# lab_2_pankov_boost.net
KiCad netlist of a schematic drawn in Altium Designer
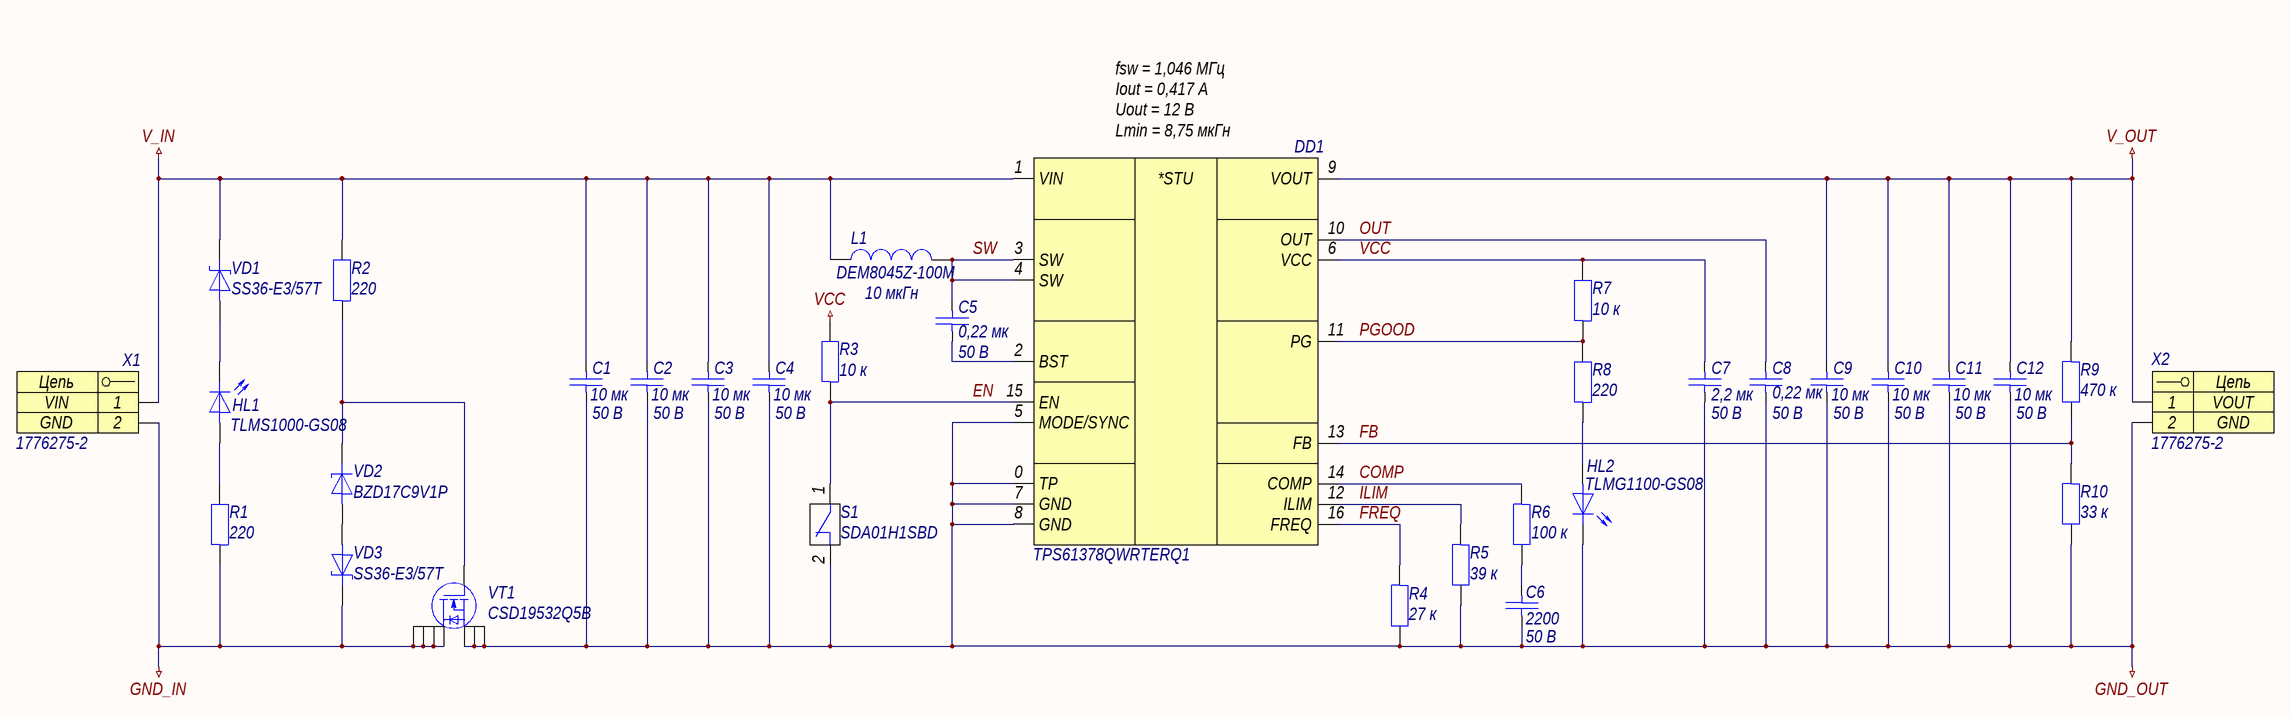
[diagram p0: lab_2_pankov_boost.SchDoc]

(export (version "E")
  (design (tool "Eeschema 10.0.6"))
  (components
    (comp (ref "C1")
      (value "10 мк")
      (footprint "C0805")
      (description "=Описание")
      (fields (field (name "НАПРЯЖЕНИЕ") "50 В"))
      (libsource (lib "Database_Students") (part "C-NONPOLAR"))
    )
    (comp (ref "C2")
      (value "10 мк")
      (footprint "C0805")
      (description "=Описание")
      (fields (field (name "НАПРЯЖЕНИЕ") "50 В"))
      (libsource (lib "Database_Students") (part "C-NONPOLAR"))
    )
    (comp (ref "C3")
      (value "10 мк")
      (footprint "C0805")
      (description "=Описание")
      (fields (field (name "НАПРЯЖЕНИЕ") "50 В"))
      (libsource (lib "Database_Students") (part "C-NONPOLAR"))
    )
    (comp (ref "C4")
      (value "10 мк")
      (footprint "C0805")
      (description "=Описание")
      (fields (field (name "НАПРЯЖЕНИЕ") "50 В"))
      (libsource (lib "Database_Students") (part "C-NONPOLAR"))
    )
    (comp (ref "C5")
      (value "0,22 мк")
      (footprint "C0603")
      (description "=Описание")
      (fields (field (name "НАПРЯЖЕНИЕ") "50 В"))
      (libsource (lib "Database_Students") (part "C-NONPOLAR"))
    )
    (comp (ref "C6")
      (value "2200")
      (footprint "C0603")
      (description "=Описание")
      (fields (field (name "НАПРЯЖЕНИЕ") "50 В"))
      (libsource (lib "Database_Students") (part "C-NONPOLAR"))
    )
    (comp (ref "C7")
      (value "2,2 мк")
      (footprint "C0603")
      (description "=Описание")
      (fields (field (name "НАПРЯЖЕНИЕ") "50 В"))
      (libsource (lib "Database_Students") (part "C-NONPOLAR"))
    )
    (comp (ref "C8")
      (value "0,22 мк")
      (footprint "C0603")
      (description "=Описание")
      (fields (field (name "НАПРЯЖЕНИЕ") "50 В"))
      (libsource (lib "Database_Students") (part "C-NONPOLAR"))
    )
    (comp (ref "C9")
      (value "10 мк")
      (footprint "C0805")
      (description "=Описание")
      (fields (field (name "НАПРЯЖЕНИЕ") "50 В"))
      (libsource (lib "Database_Students") (part "C-NONPOLAR"))
    )
    (comp (ref "C10")
      (value "10 мк")
      (footprint "C0805")
      (description "=Описание")
      (fields (field (name "НАПРЯЖЕНИЕ") "50 В"))
      (libsource (lib "Database_Students") (part "C-NONPOLAR"))
    )
    (comp (ref "C11")
      (value "10 мк")
      (footprint "C0805")
      (description "=Описание")
      (fields (field (name "НАПРЯЖЕНИЕ") "50 В"))
      (libsource (lib "Database_Students") (part "C-NONPOLAR"))
    )
    (comp (ref "C12")
      (value "10 мк")
      (footprint "C0805")
      (description "=Описание")
      (fields (field (name "НАПРЯЖЕНИЕ") "50 В"))
      (libsource (lib "Database_Students") (part "C-NONPOLAR"))
    )
    (comp (ref "DD1")
      (value "TPS61378QWRTERQ1")
      (footprint "QFN-16-3X3")
      (description "=Описание")
      (libsource (lib "Database_Students") (part "TPS61378QWRTERQ1"))
    )
    (comp (ref "HL1")
      (value "TLMS1000-GS08")
      (footprint "HL0603")
      (description "=Описание")
      (libsource (lib "Database_Students") (part "HL-COMMON"))
    )
    (comp (ref "HL2")
      (value "TLMG1100-GS08")
      (footprint "HL0603")
      (description "=Описание")
      (libsource (lib "Database_Students") (part "HL-COMMON"))
    )
    (comp (ref "L1")
      (value "DEM8045Z-100M")
      (footprint "DEM-2-800X800X450")
      (description "=Описание")
      (fields (field (name "ИНДУКТИВНОСТЬ") "10 мкГн"))
      (libsource (lib "Database_Students") (part "INDUCTOR-COMMON"))
    )
    (comp (ref "R1")
      (value "220")
      (footprint "R0603")
      (description "=Описание")
      (libsource (lib "Database_Students") (part "R-COMMON"))
    )
    (comp (ref "R2")
      (value "220")
      (footprint "R0603")
      (description "=Описание")
      (libsource (lib "Database_Students") (part "R-COMMON"))
    )
    (comp (ref "R3")
      (value "10 к")
      (footprint "R0603")
      (description "=Описание")
      (libsource (lib "Database_Students") (part "R-COMMON"))
    )
    (comp (ref "R4")
      (value "27 к")
      (footprint "R0603")
      (description "=Описание")
      (libsource (lib "Database_Students") (part "R-COMMON"))
    )
    (comp (ref "R5")
      (value "39 к")
      (footprint "R0603")
      (description "=Описание")
      (libsource (lib "Database_Students") (part "R-COMMON"))
    )
    (comp (ref "R6")
      (value "100 к")
      (footprint "R0603")
      (description "=Описание")
      (libsource (lib "Database_Students") (part "R-COMMON"))
    )
    (comp (ref "R7")
      (value "10 к")
      (footprint "R0603")
      (description "=Описание")
      (libsource (lib "Database_Students") (part "R-COMMON"))
    )
    (comp (ref "R8")
      (value "220")
      (footprint "R0603")
      (description "=Описание")
      (libsource (lib "Database_Students") (part "R-COMMON"))
    )
    (comp (ref "R9")
      (value "470 к")
      (footprint "R0603")
      (description "=Описание")
      (libsource (lib "Database_Students") (part "R-COMMON"))
    )
    (comp (ref "R10")
      (value "33 к")
      (footprint "R0603")
      (description "=Описание")
      (libsource (lib "Database_Students") (part "R-COMMON"))
    )
    (comp (ref "S1")
      (value "SDA01H1SBD")
      (footprint "DIP-SWITCH-01-452X930X545")
      (description "=Описание")
      (libsource (lib "Database_Students") (part "SWITCH-01"))
    )
    (comp (ref "VD1")
      (value "SS36-E3/57T")
      (footprint "DO-214AB")
      (description "=Описание")
      (libsource (lib "Database_Students") (part "DIODE-SCHOTTKY"))
    )
    (comp (ref "VD2")
      (value "BZD17C9V1P")
      (footprint "DO-219AB")
      (description "=Описание")
      (libsource (lib "Database_Students") (part "ZENER-DIODE"))
    )
    (comp (ref "VD3")
      (value "SS36-E3/57T")
      (footprint "DO-214AB")
      (description "=Описание")
      (libsource (lib "Database_Students") (part "DIODE-SCHOTTKY"))
    )
    (comp (ref "VT1")
      (value "CSD19532Q5B")
      (footprint "SON-8")
      (description "=Описание")
      (libsource (lib "Database_Students") (part "MOSFET_3S_4D"))
    )
    (comp (ref "X1")
      (value "1776275-2")
      (footprint "1776275-2")
      (description "=Описание")
      (libsource (lib "") (part "HEADER-2-TRM_1"))
    )
    (comp (ref "X2")
      (value "1776275-2")
      (footprint "1776275-2")
      (description "=Описание")
      (libsource (lib "Database_Students") (part "HEADER-2-TRM"))
    )
  )
  (nets
    (net (code "1") (name "/COMP") (class "Default")
      (node (ref "DD1") (pin "14") (pinfunction "COMP_14") (pintype "passive"))
      (node (ref "R6") (pin "1") (pinfunction "1_1") (pintype "passive"))
    )
    (net (code "2") (name "/EN") (class "Default")
      (node (ref "DD1") (pin "15") (pinfunction "EN_15") (pintype "passive"))
      (node (ref "R3") (pin "1") (pinfunction "1_1") (pintype "passive"))
      (node (ref "S1") (pin "1") (pinfunction "1_1") (pintype "passive"))
    )
    (net (code "3") (name "/FB") (class "Default")
      (node (ref "DD1") (pin "13") (pinfunction "FB_13") (pintype "passive"))
      (node (ref "R10") (pin "1") (pinfunction "1_1") (pintype "passive"))
      (node (ref "R9") (pin "2") (pinfunction "2_2") (pintype "passive"))
    )
    (net (code "4") (name "/FREQ") (class "Default")
      (node (ref "DD1") (pin "16") (pinfunction "FREQ_16") (pintype "passive"))
      (node (ref "R4") (pin "1") (pinfunction "1_1") (pintype "passive"))
    )
    (net (code "5") (name "/ILIM") (class "Default")
      (node (ref "DD1") (pin "12") (pinfunction "ILIM_12") (pintype "passive"))
      (node (ref "R5") (pin "1") (pinfunction "1_1") (pintype "passive"))
    )
    (net (code "6") (name "/OUT") (class "Default")
      (node (ref "C8") (pin "1") (pinfunction "1_1") (pintype "passive"))
      (node (ref "DD1") (pin "10") (pinfunction "OUT_10") (pintype "passive"))
    )
    (net (code "7") (name "/PGOOD") (class "Default")
      (node (ref "DD1") (pin "11") (pinfunction "PG_11") (pintype "passive"))
      (node (ref "R7") (pin "1") (pinfunction "1_1") (pintype "passive"))
      (node (ref "R8") (pin "2") (pinfunction "2_2") (pintype "passive"))
    )
    (net (code "8") (name "/SW") (class "Default")
      (node (ref "C5") (pin "1") (pinfunction "1_1") (pintype "passive"))
      (node (ref "DD1") (pin "3") (pinfunction "SW_3") (pintype "passive"))
      (node (ref "DD1") (pin "4") (pinfunction "SW_4") (pintype "passive"))
      (node (ref "L1") (pin "2") (pinfunction "2_2") (pintype "passive"))
    )
    (net (code "9") (name "GND_IN") (class "Default")
      (node (ref "R1") (pin "1") (pinfunction "1_1") (pintype "passive"))
      (node (ref "VD3") (pin "1") (pinfunction "1_1") (pintype "passive"))
      (node (ref "VT1") (pin "D") (pinfunction "D_D") (pintype "passive"))
      (node (ref "X1") (pin "2") (pinfunction "2_2") (pintype "passive"))
    )
    (net (code "10") (name "GND_OUT") (class "Default")
      (node (ref "C1") (pin "2") (pinfunction "2_2") (pintype "passive"))
      (node (ref "C10") (pin "2") (pinfunction "2_2") (pintype "passive"))
      (node (ref "C11") (pin "2") (pinfunction "2_2") (pintype "passive"))
      (node (ref "C12") (pin "2") (pinfunction "2_2") (pintype "passive"))
      (node (ref "C2") (pin "2") (pinfunction "2_2") (pintype "passive"))
      (node (ref "C3") (pin "2") (pinfunction "2_2") (pintype "passive"))
      (node (ref "C4") (pin "2") (pinfunction "2_2") (pintype "passive"))
      (node (ref "C6") (pin "1") (pinfunction "1_1") (pintype "passive"))
      (node (ref "C7") (pin "2") (pinfunction "2_2") (pintype "passive"))
      (node (ref "C8") (pin "2") (pinfunction "2_2") (pintype "passive"))
      (node (ref "C9") (pin "2") (pinfunction "2_2") (pintype "passive"))
      (node (ref "DD1") (pin "0") (pinfunction "TP_0") (pintype "passive"))
      (node (ref "DD1") (pin "5") (pinfunction "MODE/SYNC_5") (pintype "passive"))
      (node (ref "DD1") (pin "7") (pinfunction "GND_7") (pintype "passive"))
      (node (ref "DD1") (pin "8") (pinfunction "GND_8") (pintype "passive"))
      (node (ref "HL2") (pin "1") (pinfunction "1_1") (pintype "passive"))
      (node (ref "R10") (pin "2") (pinfunction "2_2") (pintype "passive"))
      (node (ref "R4") (pin "2") (pinfunction "2_2") (pintype "passive"))
      (node (ref "R5") (pin "2") (pinfunction "2_2") (pintype "passive"))
      (node (ref "S1") (pin "2") (pinfunction "2_2") (pintype "passive"))
      (node (ref "VT1") (pin "S") (pinfunction "S_S") (pintype "passive"))
      (node (ref "X2") (pin "2") (pinfunction "2_2") (pintype "passive"))
    )
    (net (code "11") (name "Net-(C6-Pad2)") (class "Default")
      (node (ref "C6") (pin "2") (pinfunction "2_2") (pintype "passive"))
      (node (ref "R6") (pin "2") (pinfunction "2_2") (pintype "passive"))
    )
    (net (code "12") (name "Net-(DD1-BST)") (class "Default")
      (node (ref "C5") (pin "2") (pinfunction "2_2") (pintype "passive"))
      (node (ref "DD1") (pin "2") (pinfunction "BST_2") (pintype "passive"))
    )
    (net (code "13") (name "Net-(HL1-Pad1)") (class "Default")
      (node (ref "HL1") (pin "1") (pinfunction "1_1") (pintype "passive"))
      (node (ref "VD1") (pin "2") (pinfunction "2_2") (pintype "passive"))
    )
    (net (code "14") (name "Net-(HL1-Pad2)") (class "Default")
      (node (ref "HL1") (pin "2") (pinfunction "2_2") (pintype "passive"))
      (node (ref "R1") (pin "2") (pinfunction "2_2") (pintype "passive"))
    )
    (net (code "15") (name "Net-(HL2-Pad2)") (class "Default")
      (node (ref "HL2") (pin "2") (pinfunction "2_2") (pintype "passive"))
      (node (ref "R8") (pin "1") (pinfunction "1_1") (pintype "passive"))
    )
    (net (code "16") (name "Net-(R2-Pad1)") (class "Default")
      (node (ref "R2") (pin "1") (pinfunction "1_1") (pintype "passive"))
      (node (ref "VD2") (pin "1") (pinfunction "1_1") (pintype "passive"))
      (node (ref "VT1") (pin "G") (pinfunction "G_G") (pintype "passive"))
    )
    (net (code "17") (name "Net-(VD2-Pad2)") (class "Default")
      (node (ref "VD2") (pin "2") (pinfunction "2_2") (pintype "passive"))
      (node (ref "VD3") (pin "2") (pinfunction "2_2") (pintype "passive"))
    )
    (net (code "18") (name "VCC") (class "Default")
      (node (ref "C7") (pin "1") (pinfunction "1_1") (pintype "passive"))
      (node (ref "DD1") (pin "6") (pinfunction "VCC_6") (pintype "passive"))
      (node (ref "R3") (pin "2") (pinfunction "2_2") (pintype "passive"))
      (node (ref "R7") (pin "2") (pinfunction "2_2") (pintype "passive"))
    )
    (net (code "19") (name "V_IN") (class "Default")
      (node (ref "C1") (pin "1") (pinfunction "1_1") (pintype "passive"))
      (node (ref "C2") (pin "1") (pinfunction "1_1") (pintype "passive"))
      (node (ref "C3") (pin "1") (pinfunction "1_1") (pintype "passive"))
      (node (ref "C4") (pin "1") (pinfunction "1_1") (pintype "passive"))
      (node (ref "DD1") (pin "1") (pinfunction "VIN_1") (pintype "passive"))
      (node (ref "L1") (pin "1") (pinfunction "1_1") (pintype "passive"))
      (node (ref "R2") (pin "2") (pinfunction "2_2") (pintype "passive"))
      (node (ref "VD1") (pin "1") (pinfunction "1_1") (pintype "passive"))
      (node (ref "X1") (pin "1") (pinfunction "1_1") (pintype "passive"))
    )
    (net (code "20") (name "V_OUT") (class "Default")
      (node (ref "C10") (pin "1") (pinfunction "1_1") (pintype "passive"))
      (node (ref "C11") (pin "1") (pinfunction "1_1") (pintype "passive"))
      (node (ref "C12") (pin "1") (pinfunction "1_1") (pintype "passive"))
      (node (ref "C9") (pin "1") (pinfunction "1_1") (pintype "passive"))
      (node (ref "DD1") (pin "9") (pinfunction "VOUT_9") (pintype "passive"))
      (node (ref "R9") (pin "1") (pinfunction "1_1") (pintype "passive"))
      (node (ref "X2") (pin "1") (pinfunction "1_1") (pintype "passive"))
    )
  )
)
